# 467444_130_3_3.net
KiCad netlist of a schematic drawn in Altium Designer
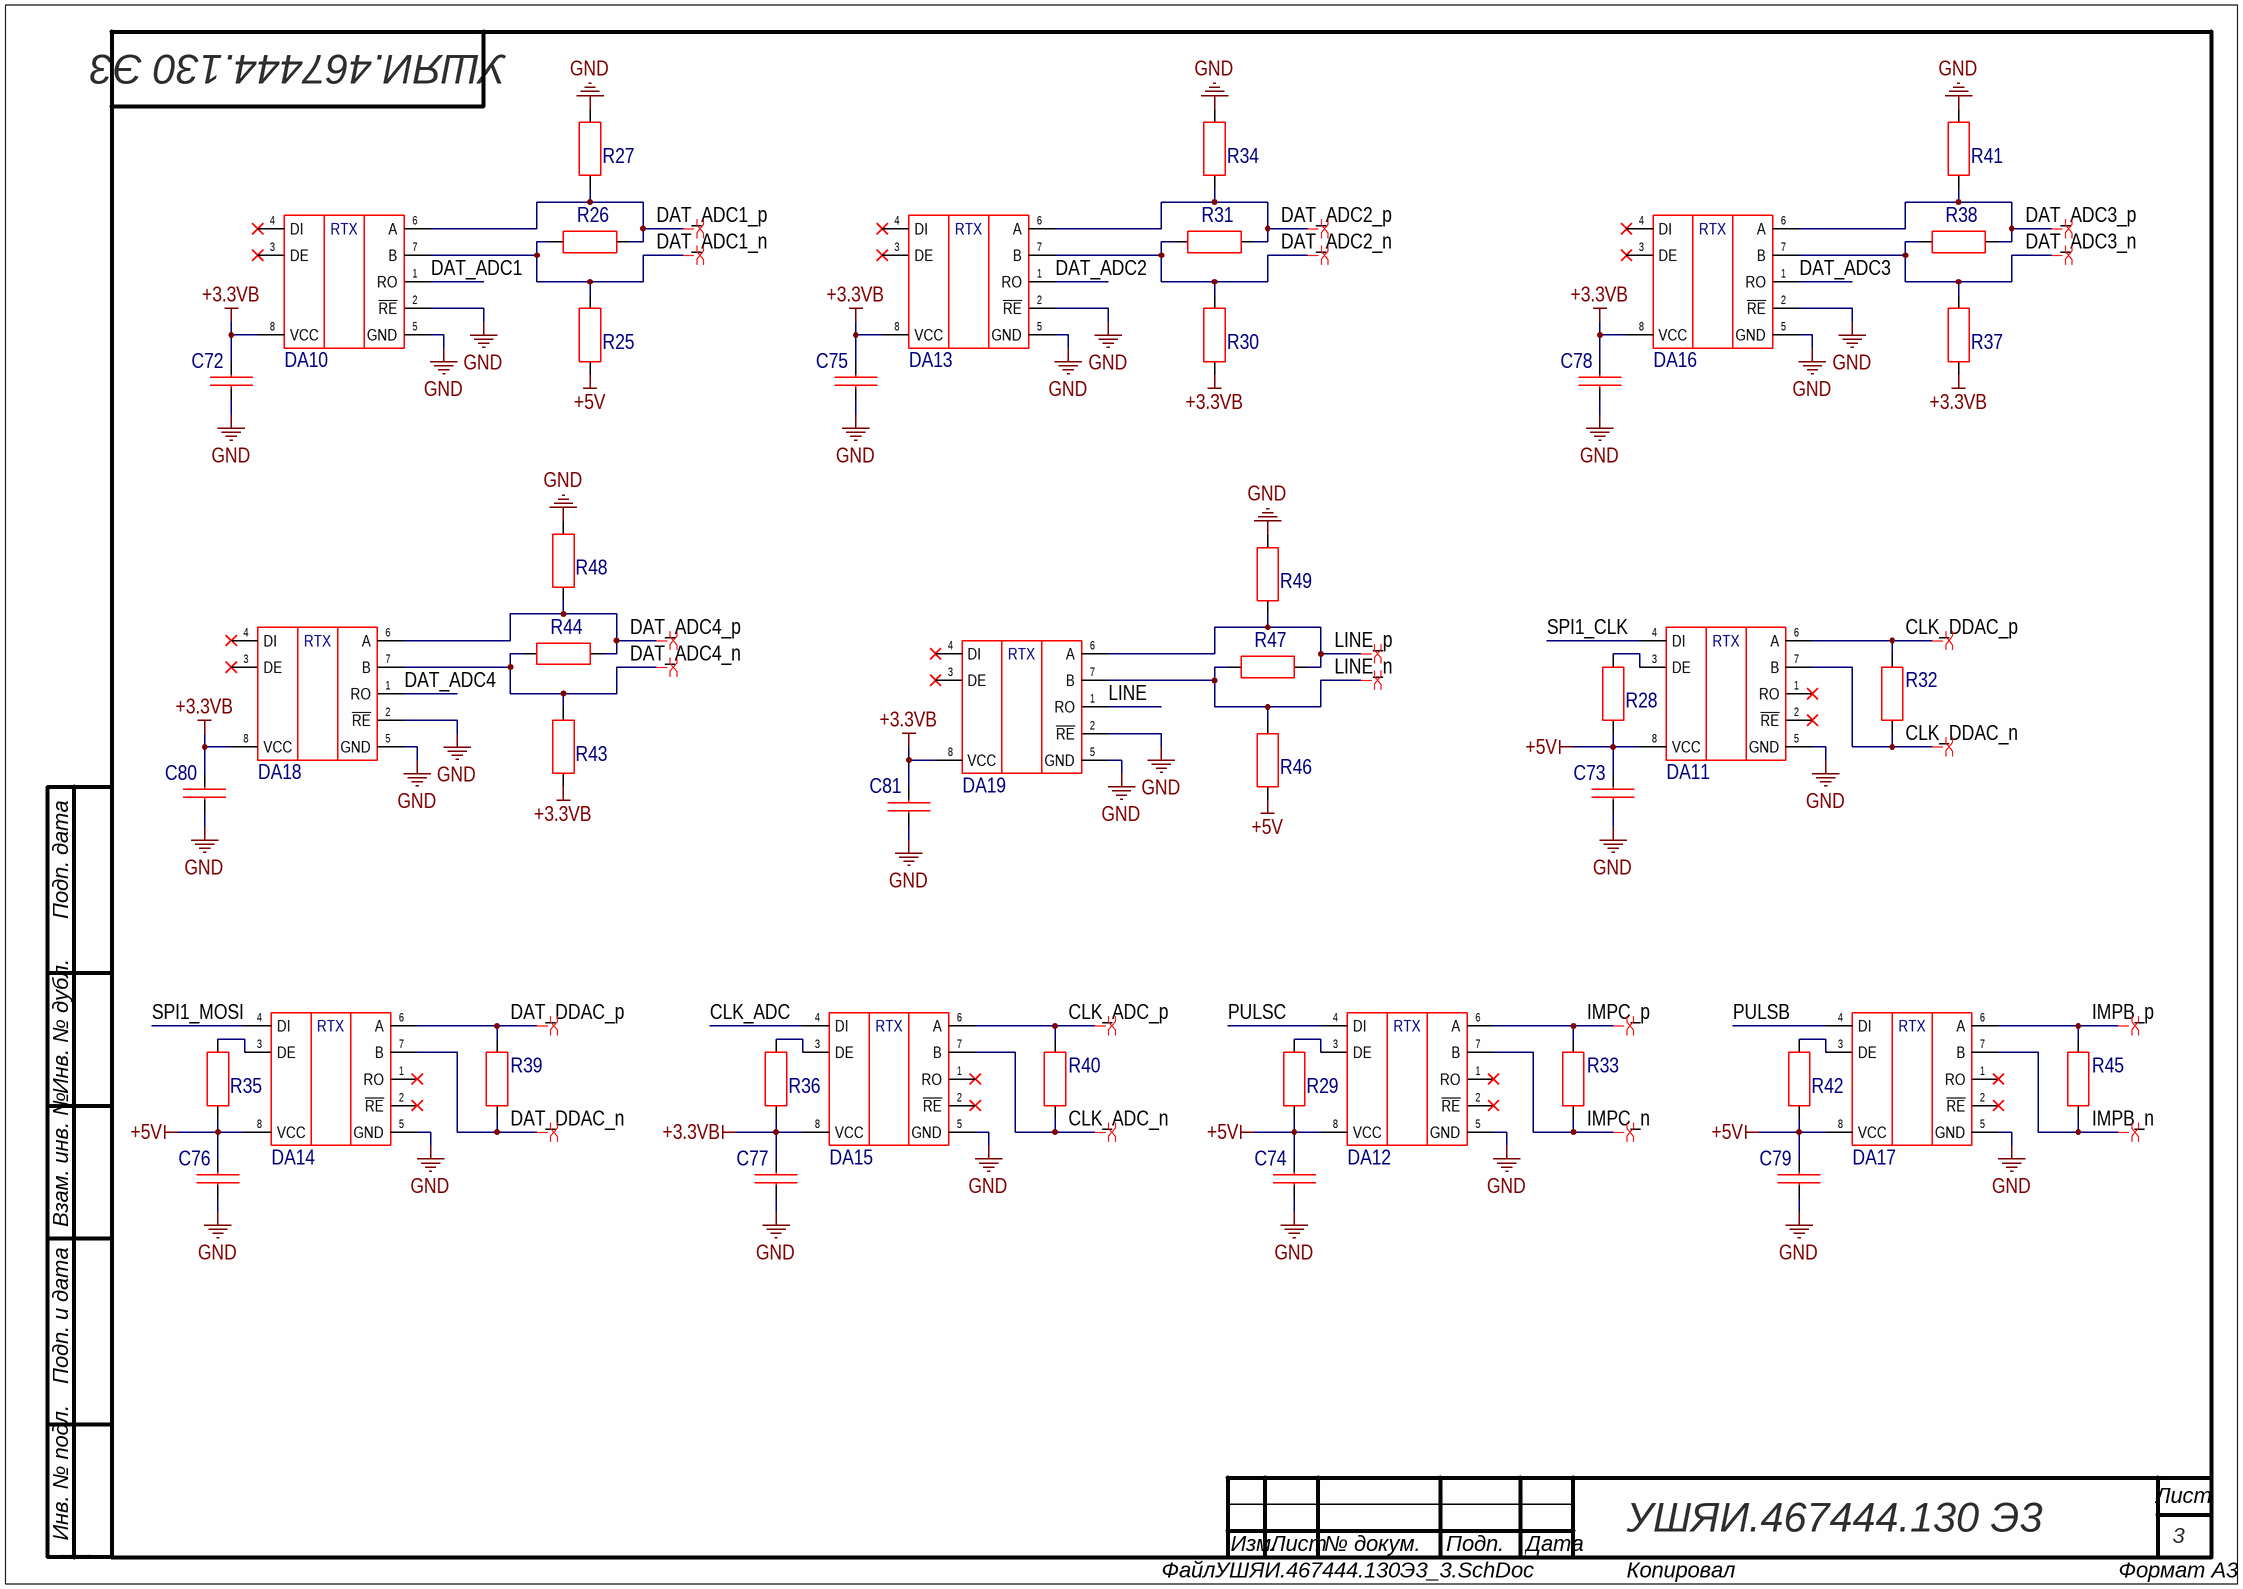
[diagram p0: УШЯИ.467444.130Э3_3.SchDoc]

(export (version "E")
  (design (tool "Eeschema 10.0.6"))
  (components
    (comp (ref "C72")
      (value "0,1 µF")
      (footprint "C_0805 [2012 Metric]")
      (description "Неполярный конденсатор")
      (fields (field (name "MANUFACTURER") "Murata") (field (name "VOLTAGE") "50V"))
      (libsource (lib "lib") (part "C_const"))
    )
    (comp (ref "C73")
      (value "0,1 µF")
      (footprint "C_0805 [2012 Metric]")
      (description "Неполярный конденсатор")
      (fields (field (name "MANUFACTURER") "Murata") (field (name "VOLTAGE") "50V"))
      (libsource (lib "lib") (part "C_const"))
    )
    (comp (ref "C74")
      (value "0,1 µF")
      (footprint "C_0805 [2012 Metric]")
      (description "Неполярный конденсатор")
      (fields (field (name "MANUFACTURER") "Murata") (field (name "VOLTAGE") "50V"))
      (libsource (lib "lib") (part "C_const"))
    )
    (comp (ref "C75")
      (value "0,1 µF")
      (footprint "C_0805 [2012 Metric]")
      (description "Неполярный конденсатор")
      (fields (field (name "MANUFACTURER") "Murata") (field (name "VOLTAGE") "50V"))
      (libsource (lib "lib") (part "C_const"))
    )
    (comp (ref "C76")
      (value "0,1 µF")
      (footprint "C_0805 [2012 Metric]")
      (description "Неполярный конденсатор")
      (fields (field (name "MANUFACTURER") "Murata") (field (name "VOLTAGE") "50V"))
      (libsource (lib "lib") (part "C_const"))
    )
    (comp (ref "C77")
      (value "0,1 µF")
      (footprint "C_0805 [2012 Metric]")
      (description "Неполярный конденсатор")
      (fields (field (name "MANUFACTURER") "Murata") (field (name "VOLTAGE") "50V"))
      (libsource (lib "lib") (part "C_const"))
    )
    (comp (ref "C78")
      (value "0,1 µF")
      (footprint "C_0805 [2012 Metric]")
      (description "Неполярный конденсатор")
      (fields (field (name "MANUFACTURER") "Murata") (field (name "VOLTAGE") "50V"))
      (libsource (lib "lib") (part "C_const"))
    )
    (comp (ref "C79")
      (value "0,1 µF")
      (footprint "C_0805 [2012 Metric]")
      (description "Неполярный конденсатор")
      (fields (field (name "MANUFACTURER") "Murata") (field (name "VOLTAGE") "50V"))
      (libsource (lib "lib") (part "C_const"))
    )
    (comp (ref "C80")
      (value "0,1 µF")
      (footprint "C_0805 [2012 Metric]")
      (description "Неполярный конденсатор")
      (fields (field (name "MANUFACTURER") "Murata") (field (name "VOLTAGE") "50V"))
      (libsource (lib "lib") (part "C_const"))
    )
    (comp (ref "C81")
      (value "0,1 µF")
      (footprint "C_0805 [2012 Metric]")
      (description "Неполярный конденсатор")
      (fields (field (name "MANUFACTURER") "Murata") (field (name "VOLTAGE") "50V"))
      (libsource (lib "lib") (part "C_const"))
    )
    (comp (ref "DA10")
      (value "SN65HVD75D")
      (footprint "SOIC-8_1.27_5x4x1.75")
      (description "IC, RS422 / RS485 Transceiver IC, 1 Driver, 1 Receiver, 3 V to 3.6 V, -40°C to 125°C, SOIC-8")
      (fields (field (name "MANUFACTURER") "Texas Instruments"))
      (libsource (lib "lib") (part "ADM483"))
    )
    (comp (ref "DA11")
      (value "ADM483AR")
      (footprint "SOIC-8_1.27_5x4x1.75")
      (description "IC, Transceiver, RS422/RS485, 1 Driver, 1 Receiver, 4.75 V to 5.25 V, -40°C to 125°C")
      (fields (field (name "MANUFACTURER") "Analog Devices"))
      (libsource (lib "lib") (part "ADM483"))
    )
    (comp (ref "DA12")
      (value "ADM483AR")
      (footprint "SOIC-8_1.27_5x4x1.75")
      (description "IC, Transceiver, RS422/RS485, 1 Driver, 1 Receiver, 4.75 V to 5.25 V, -40°C to 125°C")
      (fields (field (name "MANUFACTURER") "Analog Devices"))
      (libsource (lib "lib") (part "ADM483"))
    )
    (comp (ref "DA13")
      (value "SN65HVD75D")
      (footprint "SOIC-8_1.27_5x4x1.75")
      (description "IC, RS422 / RS485 Transceiver IC, 1 Driver, 1 Receiver, 3 V to 3.6 V, -40°C to 125°C, SOIC-8")
      (fields (field (name "MANUFACTURER") "Texas Instruments"))
      (libsource (lib "lib") (part "ADM483"))
    )
    (comp (ref "DA14")
      (value "ADM483AR")
      (footprint "SOIC-8_1.27_5x4x1.75")
      (description "IC, Transceiver, RS422/RS485, 1 Driver, 1 Receiver, 4.75 V to 5.25 V, -40°C to 125°C")
      (fields (field (name "MANUFACTURER") "Analog Devices"))
      (libsource (lib "lib") (part "ADM483"))
    )
    (comp (ref "DA15")
      (value "SN65HVD75D")
      (footprint "SOIC-8_1.27_5x4x1.75")
      (description "IC, RS422 / RS485 Transceiver IC, 1 Driver, 1 Receiver, 3 V to 3.6 V, -40°C to 125°C, SOIC-8")
      (fields (field (name "MANUFACTURER") "Texas Instruments"))
      (libsource (lib "lib") (part "ADM483"))
    )
    (comp (ref "DA16")
      (value "SN65HVD75D")
      (footprint "SOIC-8_1.27_5x4x1.75")
      (description "IC, RS422 / RS485 Transceiver IC, 1 Driver, 1 Receiver, 3 V to 3.6 V, -40°C to 125°C, SOIC-8")
      (fields (field (name "MANUFACTURER") "Texas Instruments"))
      (libsource (lib "lib") (part "ADM483"))
    )
    (comp (ref "DA17")
      (value "ADM483AR")
      (footprint "SOIC-8_1.27_5x4x1.75")
      (description "IC, Transceiver, RS422/RS485, 1 Driver, 1 Receiver, 4.75 V to 5.25 V, -40°C to 125°C")
      (fields (field (name "MANUFACTURER") "Analog Devices"))
      (libsource (lib "lib") (part "ADM483"))
    )
    (comp (ref "DA18")
      (value "SN65HVD75D")
      (footprint "SOIC-8_1.27_5x4x1.75")
      (description "IC, RS422 / RS485 Transceiver IC, 1 Driver, 1 Receiver, 3 V to 3.6 V, -40°C to 125°C, SOIC-8")
      (fields (field (name "MANUFACTURER") "Texas Instruments"))
      (libsource (lib "lib") (part "ADM483"))
    )
    (comp (ref "DA19")
      (value "SN65HVD75D")
      (footprint "SOIC-8_1.27_5x4x1.75")
      (description "IC, RS422 / RS485 Transceiver IC, 1 Driver, 1 Receiver, 3 V to 3.6 V, -40°C to 125°C, SOIC-8")
      (fields (field (name "MANUFACTURER") "Texas Instruments"))
      (libsource (lib "lib") (part "ADM483"))
    )
    (comp (ref "R25")
      (value "1k")
      (footprint "R_1206 [3216 Metric]")
      (fields (field (name "TOLERANCE") "±5%"))
      (libsource (lib "lib") (part "R_Const"))
    )
    (comp (ref "R26")
      (value "100R")
      (footprint "R_0805 [2012 Metric]")
      (fields (field (name "TOLERANCE") "±5%"))
      (libsource (lib "lib") (part "R_Const"))
    )
    (comp (ref "R27")
      (value "1k")
      (footprint "R_1206 [3216 Metric]")
      (fields (field (name "TOLERANCE") "±5%"))
      (libsource (lib "lib") (part "R_Const"))
    )
    (comp (ref "R28")
      (value "10k")
      (footprint "R_0805 [2012 Metric]")
      (fields (field (name "TOLERANCE") "±5%"))
      (libsource (lib "lib") (part "R_Const"))
    )
    (comp (ref "R29")
      (value "10k")
      (footprint "R_0805 [2012 Metric]")
      (fields (field (name "TOLERANCE") "±5%"))
      (libsource (lib "lib") (part "R_Const"))
    )
    (comp (ref "R30")
      (value "100R")
      (footprint "R_0805 [2012 Metric]")
      (fields (field (name "TOLERANCE") "±5%"))
      (libsource (lib "lib") (part "R_Const"))
    )
    (comp (ref "R31")
      (value "100R")
      (footprint "R_0805 [2012 Metric]")
      (fields (field (name "TOLERANCE") "±5%"))
      (libsource (lib "lib") (part "R_Const"))
    )
    (comp (ref "R32")
      (value "100R")
      (footprint "R_0805 [2012 Metric]")
      (fields (field (name "TOLERANCE") "±5%"))
      (libsource (lib "lib") (part "R_Const"))
    )
    (comp (ref "R33")
      (value "100R")
      (footprint "R_0805 [2012 Metric]")
      (fields (field (name "TOLERANCE") "±5%"))
      (libsource (lib "lib") (part "R_Const"))
    )
    (comp (ref "R34")
      (value "1k")
      (footprint "R_1206 [3216 Metric]")
      (fields (field (name "TOLERANCE") "±5%"))
      (libsource (lib "lib") (part "R_Const"))
    )
    (comp (ref "R35")
      (value "10k")
      (footprint "R_0805 [2012 Metric]")
      (fields (field (name "TOLERANCE") "±5%"))
      (libsource (lib "lib") (part "R_Const"))
    )
    (comp (ref "R36")
      (value "10k")
      (footprint "R_0805 [2012 Metric]")
      (fields (field (name "TOLERANCE") "±5%"))
      (libsource (lib "lib") (part "R_Const"))
    )
    (comp (ref "R37")
      (value "1k")
      (footprint "R_1206 [3216 Metric]")
      (fields (field (name "TOLERANCE") "±5%"))
      (libsource (lib "lib") (part "R_Const"))
    )
    (comp (ref "R38")
      (value "100R")
      (footprint "R_0805 [2012 Metric]")
      (fields (field (name "TOLERANCE") "±5%"))
      (libsource (lib "lib") (part "R_Const"))
    )
    (comp (ref "R39")
      (value "100R")
      (footprint "R_0805 [2012 Metric]")
      (fields (field (name "TOLERANCE") "±5%"))
      (libsource (lib "lib") (part "R_Const"))
    )
    (comp (ref "R40")
      (value "100R")
      (footprint "R_0805 [2012 Metric]")
      (fields (field (name "TOLERANCE") "±5%"))
      (libsource (lib "lib") (part "R_Const"))
    )
    (comp (ref "R41")
      (value "1k")
      (footprint "R_1206 [3216 Metric]")
      (fields (field (name "TOLERANCE") "±5%"))
      (libsource (lib "lib") (part "R_Const"))
    )
    (comp (ref "R42")
      (value "10k")
      (footprint "R_0805 [2012 Metric]")
      (fields (field (name "TOLERANCE") "±5%"))
      (libsource (lib "lib") (part "R_Const"))
    )
    (comp (ref "R43")
      (value "1k")
      (footprint "R_1206 [3216 Metric]")
      (fields (field (name "TOLERANCE") "±5%"))
      (libsource (lib "lib") (part "R_Const"))
    )
    (comp (ref "R44")
      (value "100R")
      (footprint "R_0805 [2012 Metric]")
      (fields (field (name "TOLERANCE") "±5%"))
      (libsource (lib "lib") (part "R_Const"))
    )
    (comp (ref "R45")
      (value "100R")
      (footprint "R_0805 [2012 Metric]")
      (fields (field (name "TOLERANCE") "±5%"))
      (libsource (lib "lib") (part "R_Const"))
    )
    (comp (ref "R46")
      (value "1k")
      (footprint "R_1206 [3216 Metric]")
      (fields (field (name "TOLERANCE") "±5%"))
      (libsource (lib "lib") (part "R_Const"))
    )
    (comp (ref "R47")
      (value "100R")
      (footprint "R_0805 [2012 Metric]")
      (fields (field (name "TOLERANCE") "±5%"))
      (libsource (lib "lib") (part "R_Const"))
    )
    (comp (ref "R48")
      (value "1k")
      (footprint "R_1206 [3216 Metric]")
      (fields (field (name "TOLERANCE") "±5%"))
      (libsource (lib "lib") (part "R_Const"))
    )
    (comp (ref "R49")
      (value "1k")
      (footprint "R_1206 [3216 Metric]")
      (fields (field (name "TOLERANCE") "±5%"))
      (libsource (lib "lib") (part "R_Const"))
    )
  )
  (nets
    (net (code "1") (name "+3.3VB") (class "Default")
      (node (ref "C72") (pin "2") (pinfunction "2_2") (pintype "passive"))
      (node (ref "C75") (pin "2") (pinfunction "2_2") (pintype "passive"))
      (node (ref "C77") (pin "2") (pinfunction "2_2") (pintype "passive"))
      (node (ref "C78") (pin "2") (pinfunction "2_2") (pintype "passive"))
      (node (ref "C80") (pin "2") (pinfunction "2_2") (pintype "passive"))
      (node (ref "C81") (pin "2") (pinfunction "2_2") (pintype "passive"))
      (node (ref "DA10") (pin "8") (pinfunction "VCC_8") (pintype "passive"))
      (node (ref "DA13") (pin "8") (pinfunction "VCC_8") (pintype "passive"))
      (node (ref "DA15") (pin "8") (pinfunction "VCC_8") (pintype "passive"))
      (node (ref "DA16") (pin "8") (pinfunction "VCC_8") (pintype "passive"))
      (node (ref "DA18") (pin "8") (pinfunction "VCC_8") (pintype "passive"))
      (node (ref "DA19") (pin "8") (pinfunction "VCC_8") (pintype "passive"))
      (node (ref "R30") (pin "1") (pinfunction "1_1") (pintype "passive"))
      (node (ref "R36") (pin "1") (pinfunction "1_1") (pintype "passive"))
      (node (ref "R37") (pin "1") (pinfunction "1_1") (pintype "passive"))
      (node (ref "R43") (pin "1") (pinfunction "1_1") (pintype "passive"))
    )
    (net (code "2") (name "+5V") (class "Default")
      (node (ref "C73") (pin "2") (pinfunction "2_2") (pintype "passive"))
      (node (ref "C74") (pin "2") (pinfunction "2_2") (pintype "passive"))
      (node (ref "C76") (pin "2") (pinfunction "2_2") (pintype "passive"))
      (node (ref "C79") (pin "2") (pinfunction "2_2") (pintype "passive"))
      (node (ref "DA11") (pin "8") (pinfunction "VCC_8") (pintype "passive"))
      (node (ref "DA12") (pin "8") (pinfunction "VCC_8") (pintype "passive"))
      (node (ref "DA14") (pin "8") (pinfunction "VCC_8") (pintype "passive"))
      (node (ref "DA17") (pin "8") (pinfunction "VCC_8") (pintype "passive"))
      (node (ref "R25") (pin "1") (pinfunction "1_1") (pintype "passive"))
      (node (ref "R28") (pin "1") (pinfunction "1_1") (pintype "passive"))
      (node (ref "R29") (pin "1") (pinfunction "1_1") (pintype "passive"))
      (node (ref "R35") (pin "1") (pinfunction "1_1") (pintype "passive"))
      (node (ref "R42") (pin "1") (pinfunction "1_1") (pintype "passive"))
      (node (ref "R46") (pin "1") (pinfunction "1_1") (pintype "passive"))
    )
    (net (code "3") (name "/CLK_ADC") (class "Default")
      (node (ref "DA15") (pin "4") (pinfunction "DI_4") (pintype "passive"))
    )
    (net (code "4") (name "/CLK_ADC_n") (class "Default")
      (node (ref "DA15") (pin "7") (pinfunction "B_7") (pintype "passive"))
      (node (ref "R40") (pin "1") (pinfunction "1_1") (pintype "passive"))
    )
    (net (code "5") (name "/CLK_ADC_p") (class "Default")
      (node (ref "DA15") (pin "6") (pinfunction "A_6") (pintype "passive"))
      (node (ref "R40") (pin "2") (pinfunction "2_2") (pintype "passive"))
    )
    (net (code "6") (name "/CLK_DDAC_n") (class "Default")
      (node (ref "DA11") (pin "7") (pinfunction "B_7") (pintype "passive"))
      (node (ref "R32") (pin "1") (pinfunction "1_1") (pintype "passive"))
    )
    (net (code "7") (name "/CLK_DDAC_p") (class "Default")
      (node (ref "DA11") (pin "6") (pinfunction "A_6") (pintype "passive"))
      (node (ref "R32") (pin "2") (pinfunction "2_2") (pintype "passive"))
    )
    (net (code "8") (name "/DAT_ADC1") (class "Default")
      (node (ref "DA10") (pin "1") (pinfunction "RO_1") (pintype "passive"))
    )
    (net (code "9") (name "/DAT_ADC1_n") (class "Default")
      (node (ref "DA10") (pin "7") (pinfunction "B_7") (pintype "passive"))
      (node (ref "R25") (pin "2") (pinfunction "2_2") (pintype "passive"))
      (node (ref "R26") (pin "1") (pinfunction "1_1") (pintype "passive"))
    )
    (net (code "10") (name "/DAT_ADC1_p") (class "Default")
      (node (ref "DA10") (pin "6") (pinfunction "A_6") (pintype "passive"))
      (node (ref "R26") (pin "2") (pinfunction "2_2") (pintype "passive"))
      (node (ref "R27") (pin "1") (pinfunction "1_1") (pintype "passive"))
    )
    (net (code "11") (name "/DAT_ADC2") (class "Default")
      (node (ref "DA13") (pin "1") (pinfunction "RO_1") (pintype "passive"))
    )
    (net (code "12") (name "/DAT_ADC2_n") (class "Default")
      (node (ref "DA13") (pin "7") (pinfunction "B_7") (pintype "passive"))
      (node (ref "R30") (pin "2") (pinfunction "2_2") (pintype "passive"))
      (node (ref "R31") (pin "1") (pinfunction "1_1") (pintype "passive"))
    )
    (net (code "13") (name "/DAT_ADC2_p") (class "Default")
      (node (ref "DA13") (pin "6") (pinfunction "A_6") (pintype "passive"))
      (node (ref "R31") (pin "2") (pinfunction "2_2") (pintype "passive"))
      (node (ref "R34") (pin "1") (pinfunction "1_1") (pintype "passive"))
    )
    (net (code "14") (name "/DAT_ADC3") (class "Default")
      (node (ref "DA16") (pin "1") (pinfunction "RO_1") (pintype "passive"))
    )
    (net (code "15") (name "/DAT_ADC3_n") (class "Default")
      (node (ref "DA16") (pin "7") (pinfunction "B_7") (pintype "passive"))
      (node (ref "R37") (pin "2") (pinfunction "2_2") (pintype "passive"))
      (node (ref "R38") (pin "1") (pinfunction "1_1") (pintype "passive"))
    )
    (net (code "16") (name "/DAT_ADC3_p") (class "Default")
      (node (ref "DA16") (pin "6") (pinfunction "A_6") (pintype "passive"))
      (node (ref "R38") (pin "2") (pinfunction "2_2") (pintype "passive"))
      (node (ref "R41") (pin "1") (pinfunction "1_1") (pintype "passive"))
    )
    (net (code "17") (name "/DAT_ADC4") (class "Default")
      (node (ref "DA18") (pin "1") (pinfunction "RO_1") (pintype "passive"))
    )
    (net (code "18") (name "/DAT_ADC4_n") (class "Default")
      (node (ref "DA18") (pin "7") (pinfunction "B_7") (pintype "passive"))
      (node (ref "R43") (pin "2") (pinfunction "2_2") (pintype "passive"))
      (node (ref "R44") (pin "1") (pinfunction "1_1") (pintype "passive"))
    )
    (net (code "19") (name "/DAT_ADC4_p") (class "Default")
      (node (ref "DA18") (pin "6") (pinfunction "A_6") (pintype "passive"))
      (node (ref "R44") (pin "2") (pinfunction "2_2") (pintype "passive"))
      (node (ref "R48") (pin "1") (pinfunction "1_1") (pintype "passive"))
    )
    (net (code "20") (name "/DAT_DDAC_n") (class "Default")
      (node (ref "DA14") (pin "7") (pinfunction "B_7") (pintype "passive"))
      (node (ref "R39") (pin "1") (pinfunction "1_1") (pintype "passive"))
    )
    (net (code "21") (name "/DAT_DDAC_p") (class "Default")
      (node (ref "DA14") (pin "6") (pinfunction "A_6") (pintype "passive"))
      (node (ref "R39") (pin "2") (pinfunction "2_2") (pintype "passive"))
    )
    (net (code "22") (name "/IMPB_n") (class "Default")
      (node (ref "DA17") (pin "7") (pinfunction "B_7") (pintype "passive"))
      (node (ref "R45") (pin "1") (pinfunction "1_1") (pintype "passive"))
    )
    (net (code "23") (name "/IMPB_p") (class "Default")
      (node (ref "DA17") (pin "6") (pinfunction "A_6") (pintype "passive"))
      (node (ref "R45") (pin "2") (pinfunction "2_2") (pintype "passive"))
    )
    (net (code "24") (name "/IMPC_n") (class "Default")
      (node (ref "DA12") (pin "7") (pinfunction "B_7") (pintype "passive"))
      (node (ref "R33") (pin "1") (pinfunction "1_1") (pintype "passive"))
    )
    (net (code "25") (name "/IMPC_p") (class "Default")
      (node (ref "DA12") (pin "6") (pinfunction "A_6") (pintype "passive"))
      (node (ref "R33") (pin "2") (pinfunction "2_2") (pintype "passive"))
    )
    (net (code "26") (name "/LINE") (class "Default")
      (node (ref "DA19") (pin "1") (pinfunction "RO_1") (pintype "passive"))
    )
    (net (code "27") (name "/LINE_n") (class "Default")
      (node (ref "DA19") (pin "7") (pinfunction "B_7") (pintype "passive"))
      (node (ref "R46") (pin "2") (pinfunction "2_2") (pintype "passive"))
      (node (ref "R47") (pin "1") (pinfunction "1_1") (pintype "passive"))
    )
    (net (code "28") (name "/LINE_p") (class "Default")
      (node (ref "DA19") (pin "6") (pinfunction "A_6") (pintype "passive"))
      (node (ref "R47") (pin "2") (pinfunction "2_2") (pintype "passive"))
      (node (ref "R49") (pin "1") (pinfunction "1_1") (pintype "passive"))
    )
    (net (code "29") (name "/PULSB") (class "Default")
      (node (ref "DA17") (pin "4") (pinfunction "DI_4") (pintype "passive"))
    )
    (net (code "30") (name "/PULSC") (class "Default")
      (node (ref "DA12") (pin "4") (pinfunction "DI_4") (pintype "passive"))
    )
    (net (code "31") (name "/SPI1_CLK") (class "Default")
      (node (ref "DA11") (pin "4") (pinfunction "DI_4") (pintype "passive"))
    )
    (net (code "32") (name "/SPI1_MOSI") (class "Default")
      (node (ref "DA14") (pin "4") (pinfunction "DI_4") (pintype "passive"))
    )
    (net (code "33") (name "GND") (class "Default")
      (node (ref "C72") (pin "1") (pinfunction "1_1") (pintype "passive"))
      (node (ref "C73") (pin "1") (pinfunction "1_1") (pintype "passive"))
      (node (ref "C74") (pin "1") (pinfunction "1_1") (pintype "passive"))
      (node (ref "C75") (pin "1") (pinfunction "1_1") (pintype "passive"))
      (node (ref "C76") (pin "1") (pinfunction "1_1") (pintype "passive"))
      (node (ref "C77") (pin "1") (pinfunction "1_1") (pintype "passive"))
      (node (ref "C78") (pin "1") (pinfunction "1_1") (pintype "passive"))
      (node (ref "C79") (pin "1") (pinfunction "1_1") (pintype "passive"))
      (node (ref "C80") (pin "1") (pinfunction "1_1") (pintype "passive"))
      (node (ref "C81") (pin "1") (pinfunction "1_1") (pintype "passive"))
      (node (ref "DA10") (pin "2") (pinfunction "~{RE}_2") (pintype "passive"))
      (node (ref "DA10") (pin "5") (pinfunction "GND_5") (pintype "passive"))
      (node (ref "DA11") (pin "5") (pinfunction "GND_5") (pintype "passive"))
      (node (ref "DA12") (pin "5") (pinfunction "GND_5") (pintype "passive"))
      (node (ref "DA13") (pin "2") (pinfunction "~{RE}_2") (pintype "passive"))
      (node (ref "DA13") (pin "5") (pinfunction "GND_5") (pintype "passive"))
      (node (ref "DA14") (pin "5") (pinfunction "GND_5") (pintype "passive"))
      (node (ref "DA15") (pin "5") (pinfunction "GND_5") (pintype "passive"))
      (node (ref "DA16") (pin "2") (pinfunction "~{RE}_2") (pintype "passive"))
      (node (ref "DA16") (pin "5") (pinfunction "GND_5") (pintype "passive"))
      (node (ref "DA17") (pin "5") (pinfunction "GND_5") (pintype "passive"))
      (node (ref "DA18") (pin "2") (pinfunction "~{RE}_2") (pintype "passive"))
      (node (ref "DA18") (pin "5") (pinfunction "GND_5") (pintype "passive"))
      (node (ref "DA19") (pin "2") (pinfunction "~{RE}_2") (pintype "passive"))
      (node (ref "DA19") (pin "5") (pinfunction "GND_5") (pintype "passive"))
      (node (ref "R27") (pin "2") (pinfunction "2_2") (pintype "passive"))
      (node (ref "R34") (pin "2") (pinfunction "2_2") (pintype "passive"))
      (node (ref "R41") (pin "2") (pinfunction "2_2") (pintype "passive"))
      (node (ref "R48") (pin "2") (pinfunction "2_2") (pintype "passive"))
      (node (ref "R49") (pin "2") (pinfunction "2_2") (pintype "passive"))
    )
    (net (code "34") (name "Net-(DA11-DE)") (class "Default")
      (node (ref "DA11") (pin "3") (pinfunction "DE_3") (pintype "passive"))
      (node (ref "R28") (pin "2") (pinfunction "2_2") (pintype "passive"))
    )
    (net (code "35") (name "Net-(DA12-DE)") (class "Default")
      (node (ref "DA12") (pin "3") (pinfunction "DE_3") (pintype "passive"))
      (node (ref "R29") (pin "2") (pinfunction "2_2") (pintype "passive"))
    )
    (net (code "36") (name "Net-(DA14-DE)") (class "Default")
      (node (ref "DA14") (pin "3") (pinfunction "DE_3") (pintype "passive"))
      (node (ref "R35") (pin "2") (pinfunction "2_2") (pintype "passive"))
    )
    (net (code "37") (name "Net-(DA15-DE)") (class "Default")
      (node (ref "DA15") (pin "3") (pinfunction "DE_3") (pintype "passive"))
      (node (ref "R36") (pin "2") (pinfunction "2_2") (pintype "passive"))
    )
    (net (code "38") (name "Net-(DA17-DE)") (class "Default")
      (node (ref "DA17") (pin "3") (pinfunction "DE_3") (pintype "passive"))
      (node (ref "R42") (pin "2") (pinfunction "2_2") (pintype "passive"))
    )
    (net (code "39") (name "unconnected-(DA10-DE-Pad3)") (class "Default")
      (node (ref "DA10") (pin "3") (pinfunction "DE_3") (pintype "passive+no_connect"))
    )
    (net (code "40") (name "unconnected-(DA10-DI-Pad4)") (class "Default")
      (node (ref "DA10") (pin "4") (pinfunction "DI_4") (pintype "passive+no_connect"))
    )
    (net (code "41") (name "unconnected-(DA11-RO-Pad1)") (class "Default")
      (node (ref "DA11") (pin "1") (pinfunction "RO_1") (pintype "passive+no_connect"))
    )
    (net (code "42") (name "unconnected-(DA11-~{RE}-Pad2)") (class "Default")
      (node (ref "DA11") (pin "2") (pinfunction "~{RE}_2") (pintype "passive+no_connect"))
    )
    (net (code "43") (name "unconnected-(DA12-RO-Pad1)") (class "Default")
      (node (ref "DA12") (pin "1") (pinfunction "RO_1") (pintype "passive+no_connect"))
    )
    (net (code "44") (name "unconnected-(DA12-~{RE}-Pad2)") (class "Default")
      (node (ref "DA12") (pin "2") (pinfunction "~{RE}_2") (pintype "passive+no_connect"))
    )
    (net (code "45") (name "unconnected-(DA13-DE-Pad3)") (class "Default")
      (node (ref "DA13") (pin "3") (pinfunction "DE_3") (pintype "passive+no_connect"))
    )
    (net (code "46") (name "unconnected-(DA13-DI-Pad4)") (class "Default")
      (node (ref "DA13") (pin "4") (pinfunction "DI_4") (pintype "passive+no_connect"))
    )
    (net (code "47") (name "unconnected-(DA14-RO-Pad1)") (class "Default")
      (node (ref "DA14") (pin "1") (pinfunction "RO_1") (pintype "passive+no_connect"))
    )
    (net (code "48") (name "unconnected-(DA14-~{RE}-Pad2)") (class "Default")
      (node (ref "DA14") (pin "2") (pinfunction "~{RE}_2") (pintype "passive+no_connect"))
    )
    (net (code "49") (name "unconnected-(DA15-RO-Pad1)") (class "Default")
      (node (ref "DA15") (pin "1") (pinfunction "RO_1") (pintype "passive+no_connect"))
    )
    (net (code "50") (name "unconnected-(DA15-~{RE}-Pad2)") (class "Default")
      (node (ref "DA15") (pin "2") (pinfunction "~{RE}_2") (pintype "passive+no_connect"))
    )
    (net (code "51") (name "unconnected-(DA16-DE-Pad3)") (class "Default")
      (node (ref "DA16") (pin "3") (pinfunction "DE_3") (pintype "passive+no_connect"))
    )
    (net (code "52") (name "unconnected-(DA16-DI-Pad4)") (class "Default")
      (node (ref "DA16") (pin "4") (pinfunction "DI_4") (pintype "passive+no_connect"))
    )
    (net (code "53") (name "unconnected-(DA17-RO-Pad1)") (class "Default")
      (node (ref "DA17") (pin "1") (pinfunction "RO_1") (pintype "passive+no_connect"))
    )
    (net (code "54") (name "unconnected-(DA17-~{RE}-Pad2)") (class "Default")
      (node (ref "DA17") (pin "2") (pinfunction "~{RE}_2") (pintype "passive+no_connect"))
    )
    (net (code "55") (name "unconnected-(DA18-DE-Pad3)") (class "Default")
      (node (ref "DA18") (pin "3") (pinfunction "DE_3") (pintype "passive+no_connect"))
    )
    (net (code "56") (name "unconnected-(DA18-DI-Pad4)") (class "Default")
      (node (ref "DA18") (pin "4") (pinfunction "DI_4") (pintype "passive+no_connect"))
    )
    (net (code "57") (name "unconnected-(DA19-DE-Pad3)") (class "Default")
      (node (ref "DA19") (pin "3") (pinfunction "DE_3") (pintype "passive+no_connect"))
    )
    (net (code "58") (name "unconnected-(DA19-DI-Pad4)") (class "Default")
      (node (ref "DA19") (pin "4") (pinfunction "DI_4") (pintype "passive+no_connect"))
    )
  )
)
